# Amplifier_V0.net
KiCad netlist of a schematic drawn in EasyEDA
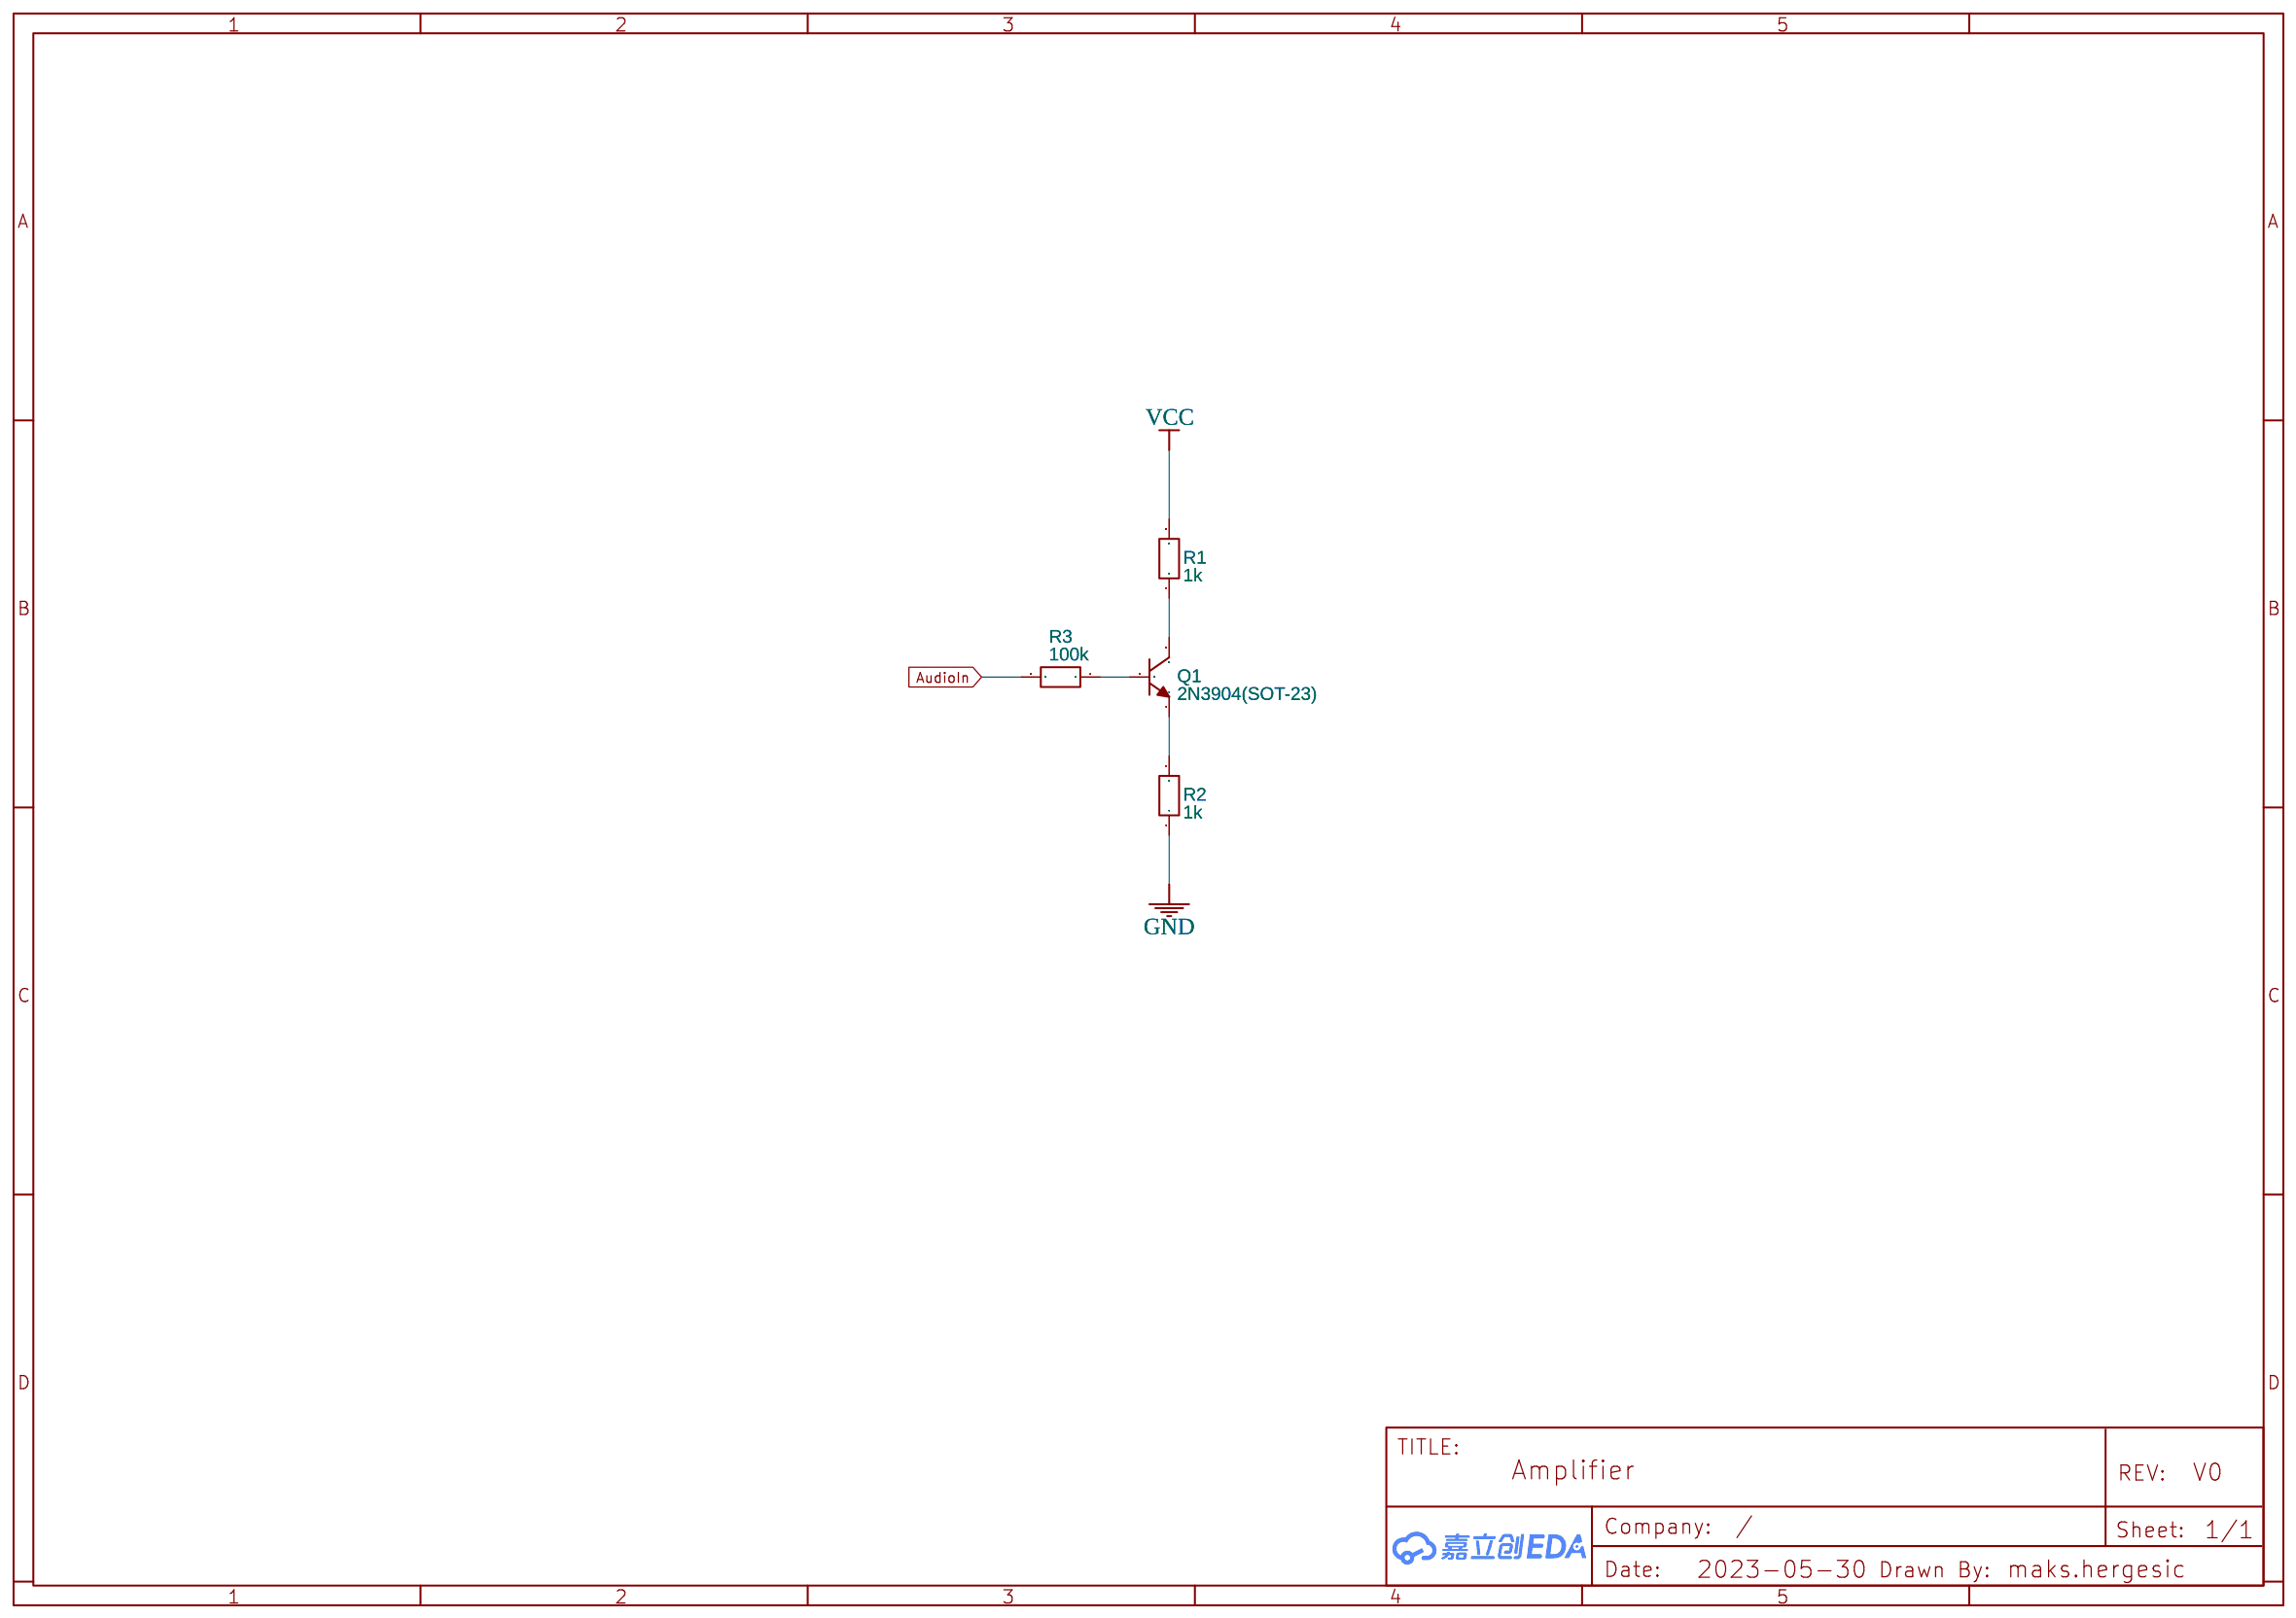
[diagram p0: schematic sheet]

(export (version "E")
  (design (tool "Eeschema 10.0.6"))
  (components
    (comp (ref "Q1")
      (value "2N3904(SOT-23)")
      (fields
        (field (name "BOM_Manufacturer Part") "2n3904S-RTK/PS")
        (field (name "BOM_Supplier Part") "C18536")
      )
      (libsource (lib "") (part "2N3904(SOT-23)"))
    )
    (comp (ref "R1") (value "1k") (libsource (lib "") (part "R_0603_EU")))
    (comp (ref "R2") (value "1k") (libsource (lib "") (part "R_0603_EU")))
    (comp (ref "R3") (value "100k") (libsource (lib "") (part "R_0603_EU_1")))
  )
  (nets
    (net (code "1") (name "AudioIn") (class "Default")
      (node (ref "R3") (pin "2") (pinfunction "2_2") (pintype "unspecified"))
    )
    (net (code "2") (name "GND") (class "Default")
      (node (ref "R2") (pin "1") (pinfunction "1_1") (pintype "unspecified"))
    )
    (net (code "3") (name "Net-(Q1-B)") (class "Default")
      (node (ref "Q1") (pin "2") (pinfunction "B_2") (pintype "input"))
      (node (ref "R3") (pin "1") (pinfunction "1_1") (pintype "unspecified"))
    )
    (net (code "4") (name "Net-(Q1-C)") (class "Default")
      (node (ref "Q1") (pin "3") (pinfunction "C_3") (pintype "input"))
      (node (ref "R1") (pin "1") (pinfunction "1_1") (pintype "unspecified"))
    )
    (net (code "5") (name "Net-(Q1-E)") (class "Default")
      (node (ref "Q1") (pin "1") (pinfunction "E_1") (pintype "input"))
      (node (ref "R2") (pin "2") (pinfunction "2_2") (pintype "unspecified"))
    )
    (net (code "6") (name "VCC") (class "Default")
      (node (ref "R1") (pin "2") (pinfunction "2_2") (pintype "unspecified"))
    )
  )
)
